# station_easyEDA.net
KiCad netlist of a schematic drawn in EasyEDA
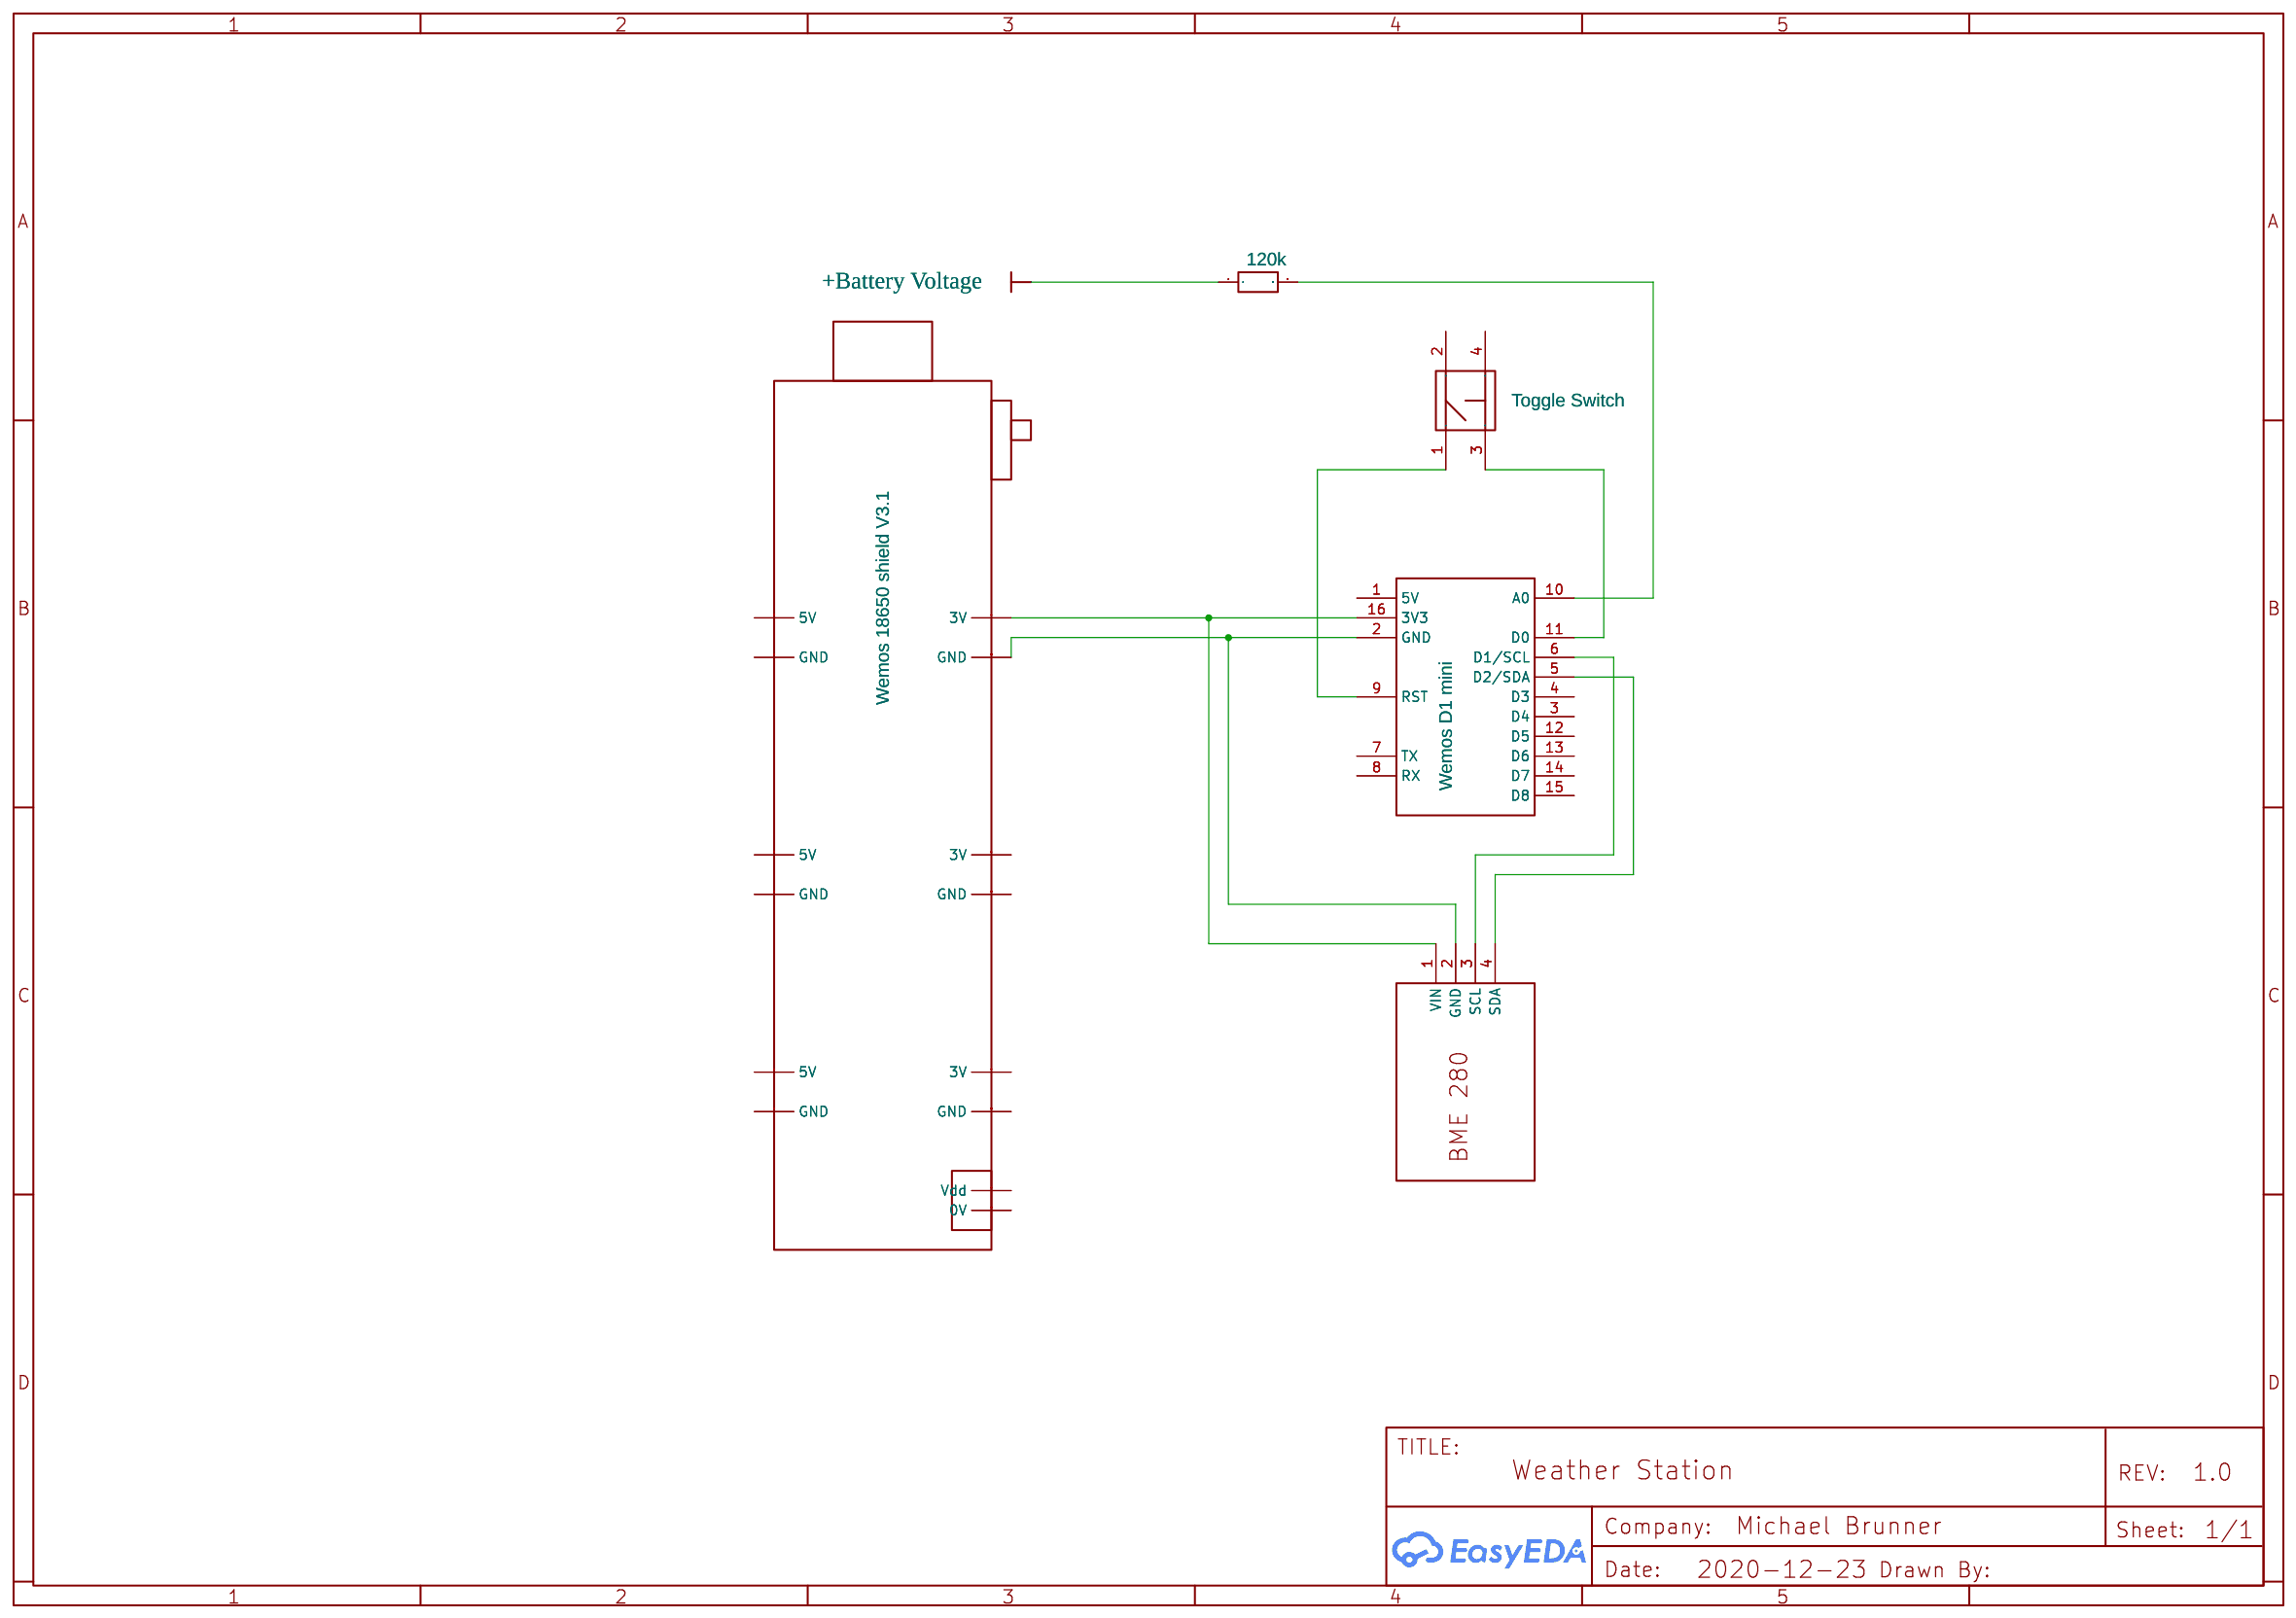
[diagram p0: schematic sheet]

(export (version "E")
  (design (tool "Eeschema 10.0.6"))
  (components
    (comp (ref "R1") (value "120k") (libsource (lib "") (part "R_0805_EU")))
    (comp (ref "U1") (value "BME 280") (libsource (lib "") (part "BME 280")))
    (comp (ref "U2")
      (value "Wemos 18650 shield V3.1")
      (fields (field (name "BOM_Manufacturer Part") "Wemos 18650 shield"))
      (libsource (lib "") (part "Wemos 18650 shield V3.1"))
    )
    (comp (ref "U3") (value "Wemos D1 mini") (libsource (lib "") (part "Wemos D1 mini")))
    (comp (ref "U4")
      (value "Toggle Switch")
      (fields (field (name "BOM_Manufacturer Part") "Push_Button_NO"))
      (libsource (lib "") (part "Push_Button"))
    )
  )
  (nets
    (net (code "1") (name "+Battery Voltage") (class "Default")
      (node (ref "R1") (pin "1") (pinfunction "1_1") (pintype "unspecified"))
    )
    (net (code "2") (name "Net-(U1-GND)") (class "Default")
      (node (ref "U1") (pin "2") (pinfunction "GND_2") (pintype "unspecified"))
      (node (ref "U2") (pin "GND") (pinfunction "GND_GND") (pintype "unspecified"))
      (node (ref "U3") (pin "2") (pinfunction "GND_2") (pintype "unspecified"))
    )
    (net (code "3") (name "Net-(U1-SCL)") (class "Default")
      (node (ref "U1") (pin "3") (pinfunction "SCL_3") (pintype "unspecified"))
      (node (ref "U3") (pin "6") (pinfunction "D1/SCL_6") (pintype "unspecified"))
    )
    (net (code "4") (name "Net-(U1-SDA)") (class "Default")
      (node (ref "U1") (pin "4") (pinfunction "SDA_4") (pintype "unspecified"))
      (node (ref "U3") (pin "5") (pinfunction "D2/SDA_5") (pintype "unspecified"))
    )
    (net (code "5") (name "Net-(U1-VIN)") (class "Default")
      (node (ref "U1") (pin "1") (pinfunction "VIN_1") (pintype "unspecified"))
      (node (ref "U2") (pin "5V") (pinfunction "3V_5V") (pintype "unspecified"))
      (node (ref "U3") (pin "16") (pinfunction "3V3_16") (pintype "unspecified"))
    )
    (net (code "6") (name "Net-(U3-A0)") (class "Default")
      (node (ref "R1") (pin "2") (pinfunction "2_2") (pintype "unspecified"))
      (node (ref "U3") (pin "10") (pinfunction "A0_10") (pintype "unspecified"))
    )
    (net (code "7") (name "Net-(U3-D0)") (class "Default")
      (node (ref "U3") (pin "11") (pinfunction "D0_11") (pintype "unspecified"))
      (node (ref "U4") (pin "3") (pinfunction "3_3") (pintype "unspecified"))
    )
    (net (code "8") (name "Net-(U3-RST)") (class "Default")
      (node (ref "U3") (pin "9") (pinfunction "RST_9") (pintype "unspecified"))
      (node (ref "U4") (pin "1") (pinfunction "1_1") (pintype "unspecified"))
    )
    (net (code "9") (name "unconnected-(U2-0V-Pad13)") (class "Default")
      (node (ref "U2") (pin "13") (pinfunction "0V_13") (pintype "unspecified"))
    )
    (net (code "10") (name "unconnected-(U2-3V-Pad5V)") (class "Default")
      (node (ref "U2") (pin "5V") (pinfunction "3V_5V") (pintype "unspecified"))
    )
    (net (code "11") (name "unconnected-(U2-3V-Pad5V)_1") (class "Default")
      (node (ref "U2") (pin "5V") (pinfunction "3V_5V") (pintype "unspecified"))
    )
    (net (code "12") (name "unconnected-(U2-5V-Pad3V)") (class "Default")
      (node (ref "U2") (pin "3V") (pinfunction "5V_3V") (pintype "unspecified"))
    )
    (net (code "13") (name "unconnected-(U2-5V-Pad3V)_1") (class "Default")
      (node (ref "U2") (pin "3V") (pinfunction "5V_3V") (pintype "unspecified"))
    )
    (net (code "14") (name "unconnected-(U2-5V-Pad3V)_2") (class "Default")
      (node (ref "U2") (pin "3V") (pinfunction "5V_3V") (pintype "unspecified"))
    )
    (net (code "15") (name "unconnected-(U2-PadGND)") (class "Default")
      (node (ref "U2") (pin "GND") (pinfunction "GND_GND") (pintype "unspecified"))
    )
    (net (code "16") (name "unconnected-(U2-PadGND)_1") (class "Default")
      (node (ref "U2") (pin "GND") (pinfunction "GND_GND") (pintype "unspecified"))
    )
    (net (code "17") (name "unconnected-(U2-PadGND)_2") (class "Default")
      (node (ref "U2") (pin "GND") (pinfunction "GND_GND") (pintype "unspecified"))
    )
    (net (code "18") (name "unconnected-(U2-PadGND)_3") (class "Default")
      (node (ref "U2") (pin "GND") (pinfunction "GND_GND") (pintype "unspecified"))
    )
    (net (code "19") (name "unconnected-(U2-PadGND)_4") (class "Default")
      (node (ref "U2") (pin "GND") (pinfunction "GND_GND") (pintype "unspecified"))
    )
    (net (code "20") (name "unconnected-(U2-Vdd-Pad14)") (class "Default")
      (node (ref "U2") (pin "14") (pinfunction "Vdd_14") (pintype "unspecified"))
    )
    (net (code "21") (name "unconnected-(U3-5V-Pad1)") (class "Default")
      (node (ref "U3") (pin "1") (pinfunction "5V_1") (pintype "unspecified"))
    )
    (net (code "22") (name "unconnected-(U3-D3-Pad4)") (class "Default")
      (node (ref "U3") (pin "4") (pinfunction "D3_4") (pintype "unspecified"))
    )
    (net (code "23") (name "unconnected-(U3-D4-Pad3)") (class "Default")
      (node (ref "U3") (pin "3") (pinfunction "D4_3") (pintype "unspecified"))
    )
    (net (code "24") (name "unconnected-(U3-D5-Pad12)") (class "Default")
      (node (ref "U3") (pin "12") (pinfunction "D5_12") (pintype "unspecified"))
    )
    (net (code "25") (name "unconnected-(U3-D6-Pad13)") (class "Default")
      (node (ref "U3") (pin "13") (pinfunction "D6_13") (pintype "unspecified"))
    )
    (net (code "26") (name "unconnected-(U3-D7-Pad14)") (class "Default")
      (node (ref "U3") (pin "14") (pinfunction "D7_14") (pintype "unspecified"))
    )
    (net (code "27") (name "unconnected-(U3-D8-Pad15)") (class "Default")
      (node (ref "U3") (pin "15") (pinfunction "D8_15") (pintype "unspecified"))
    )
    (net (code "28") (name "unconnected-(U3-RX-Pad8)") (class "Default")
      (node (ref "U3") (pin "8") (pinfunction "RX_8") (pintype "unspecified"))
    )
    (net (code "29") (name "unconnected-(U3-TX-Pad7)") (class "Default")
      (node (ref "U3") (pin "7") (pinfunction "TX_7") (pintype "unspecified"))
    )
    (net (code "30") (name "unconnected-(U4-Pad2)") (class "Default")
      (node (ref "U4") (pin "2") (pinfunction "2_2") (pintype "unspecified"))
    )
    (net (code "31") (name "unconnected-(U4-Pad4)") (class "Default")
      (node (ref "U4") (pin "4") (pinfunction "4_4") (pintype "unspecified"))
    )
  )
)
